# 07_nRF_GPIO.net
KiCad netlist of a schematic drawn in Altium Designer
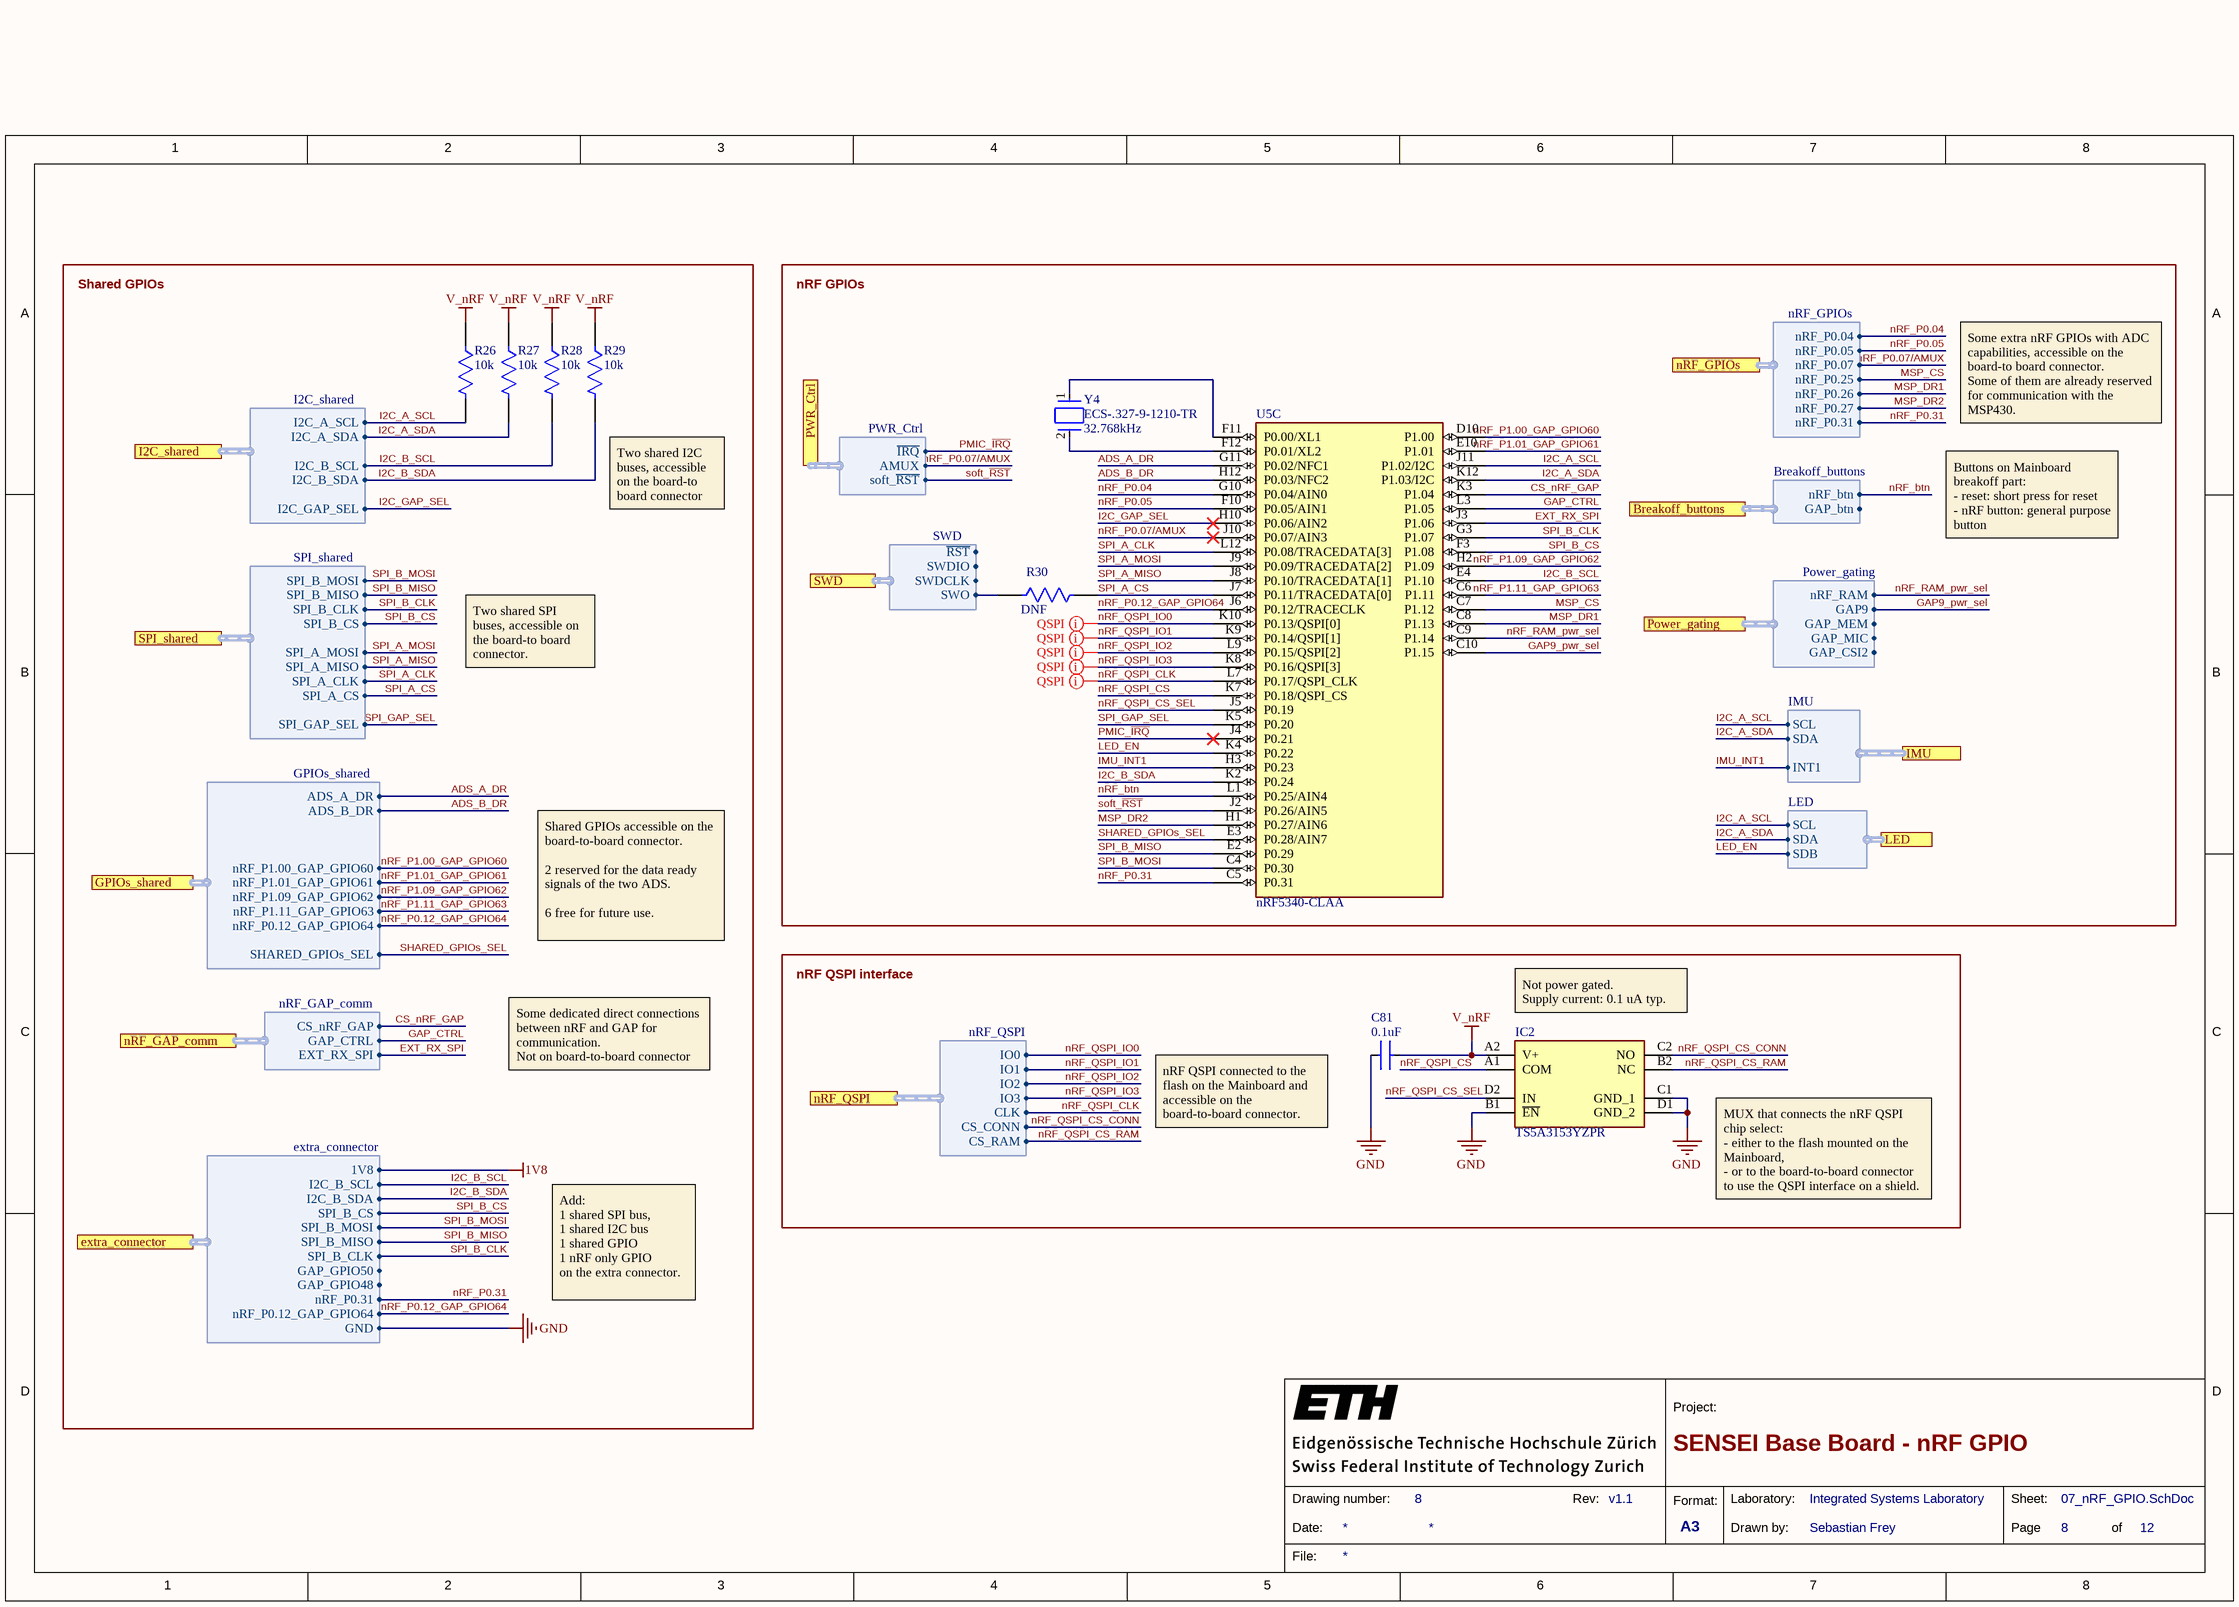
[diagram p0: 07_nRF_GPIO.SchDoc]

(export (version "E")
  (design (tool "Eeschema 10.0.6"))
  (components
    (comp (ref "C81")
      (value "GRM033Z71C104KE14D")
      (footprint "FP-GRM033-0_03-IPC_C")
      (description "Chip Multilayer Ceramic Capacitors for General Purpose, 0201, 0.10uF, X7R, 15%, 10%, 16V")
      (fields (field (name "CAPACITANCE") "0.1uF"))
      (libsource (lib "Altium Content Vault") (part "b4654b650e69147ec39a6b967a45e02"))
    )
    (comp (ref "IC2")
      (value "TS5A3153YZPR")
      (footprint "SamacSys:BGA8C50P2X4_89X189X50")
      (description "Integrated Circuit")
      (fields (field (name "MOUSER PART NUMBER") "595-TS5A3153YZPR"))
      (libsource (lib "SamacSys") (part "TS5A3153YZPR"))
    )
    (comp (ref "R26")
      (value "RMCF0201FT10K0")
      (footprint "FP-RMCF0201-IPC_C")
      (description "RES 10K OHM 1% 1/20W 0201")
      (fields (field (name "RESISTANCE") "10k") (field (name "TOLERANCE") "1%"))
      (libsource (lib "Altium Content Vault") (part "1029c3af85768c4190bb7ad29bc67b5"))
    )
    (comp (ref "R27")
      (value "RMCF0201FT10K0")
      (footprint "FP-RMCF0201-IPC_C")
      (description "RES 10K OHM 1% 1/20W 0201")
      (fields (field (name "RESISTANCE") "10k") (field (name "TOLERANCE") "1%"))
      (libsource (lib "Altium Content Vault") (part "1029c3af85768c4190bb7ad29bc67b5"))
    )
    (comp (ref "R28")
      (value "RMCF0201FT10K0")
      (footprint "FP-RMCF0201-IPC_C")
      (description "RES 10K OHM 1% 1/20W 0201")
      (fields (field (name "RESISTANCE") "10k") (field (name "TOLERANCE") "1%"))
      (libsource (lib "Altium Content Vault") (part "1029c3af85768c4190bb7ad29bc67b5"))
    )
    (comp (ref "R29")
      (value "RMCF0201FT10K0")
      (footprint "FP-RMCF0201-IPC_C")
      (description "RES 10K OHM 1% 1/20W 0201")
      (fields (field (name "RESISTANCE") "10k") (field (name "TOLERANCE") "1%"))
      (libsource (lib "Altium Content Vault") (part "1029c3af85768c4190bb7ad29bc67b5"))
    )
    (comp (ref "R30")
      (value "DNF")
      (footprint "FP-RMCF0201-IPC_C")
      (libsource (lib "Altium Content Vault") (part "1029c3af85768c4190bb7ad29bc67b5"))
    )
    (comp (ref "U5")
      (value "nRF5340-CLAA")
      (footprint "EEG_PcbLib:NRF5340_WLCSP")
      (description "Multi-protocol Bluetooth Low Energy, IEEE 802.15.4, ANT and 2.4GHz proprietary system-on-chip")
      (fields
        (field (name "MANUFACTURER") "Nordic")
        (field (name "MANUFACTURER PART NUMBER") "NRF5340-CLAA-R7")
      )
      (libsource (lib "EEG_SchLib") (part "nRF5340-CLAA"))
    )
    (comp (ref "Y4")
      (value "ECS-.327-9-1210-TR")
      (footprint "FP-ECX-1210-MFG")
      (description "CRYSTAL 32.7680KHZ 9PF SMD")
      (fields (field (name "FREQUENCY") "32.768kHz"))
      (libsource (lib "Altium Content Vault") (part "99724985039315a44fd0d1401b84e49"))
    )
  )
  (nets
    (net (code "14") (name "/ADS_A_DR") (class "Default")
      (node (ref "U5") (pin "G11") (pinfunction "P0.02/NFC1_G11") (pintype "bidirectional"))
    )
    (net (code "15") (name "/ADS_B_DR") (class "Default")
      (node (ref "U5") (pin "H12") (pinfunction "P0.03/NFC2_H12") (pintype "bidirectional"))
    )
    (net (code "16") (name "/CS_nRF_GAP") (class "Default")
      (node (ref "U5") (pin "K3") (pinfunction "P1.04_K3") (pintype "bidirectional"))
    )
    (net (code "17") (name "/EXT_RX_SPI") (class "Default")
      (node (ref "U5") (pin "J3") (pinfunction "P1.06_J3") (pintype "bidirectional"))
    )
    (net (code "18") (name "/GAP9_pwr_sel") (class "Default")
      (node (ref "U5") (pin "C10") (pinfunction "P1.15_C10") (pintype "bidirectional"))
    )
    (net (code "19") (name "/GAP_CTRL") (class "Default")
      (node (ref "U5") (pin "L3") (pinfunction "P1.05_L3") (pintype "bidirectional"))
    )
    (net (code "20") (name "/I2C_A_SCL") (class "Default")
      (node (ref "R26") (pin "2") (pinfunction "2_2") (pintype "passive"))
      (node (ref "U5") (pin "J11") (pinfunction "P1.02/I2C_J11") (pintype "bidirectional"))
    )
    (net (code "21") (name "/I2C_A_SDA") (class "Default")
      (node (ref "R27") (pin "2") (pinfunction "2_2") (pintype "passive"))
      (node (ref "U5") (pin "K12") (pinfunction "P1.03/I2C_K12") (pintype "bidirectional"))
    )
    (net (code "22") (name "/I2C_B_SCL") (class "Default")
      (node (ref "R28") (pin "2") (pinfunction "2_2") (pintype "passive"))
      (node (ref "U5") (pin "E4") (pinfunction "P1.10_E4") (pintype "bidirectional"))
    )
    (net (code "23") (name "/I2C_B_SDA") (class "Default")
      (node (ref "R29") (pin "2") (pinfunction "2_2") (pintype "passive"))
      (node (ref "U5") (pin "K2") (pinfunction "P0.24_K2") (pintype "bidirectional"))
    )
    (net (code "24") (name "/I2C_GAP_SEL") (class "Default")
      (node (ref "U5") (pin "H10") (pinfunction "P0.06/AIN2_H10") (pintype "bidirectional+no_connect"))
    )
    (net (code "25") (name "/IMU_INT1") (class "Default")
      (node (ref "U5") (pin "H3") (pinfunction "P0.23_H3") (pintype "bidirectional"))
    )
    (net (code "26") (name "/LED_EN") (class "Default")
      (node (ref "U5") (pin "K4") (pinfunction "P0.22_K4") (pintype "bidirectional"))
    )
    (net (code "27") (name "/MSP_CS") (class "Default")
      (node (ref "U5") (pin "C7") (pinfunction "P1.12_C7") (pintype "bidirectional"))
    )
    (net (code "28") (name "/MSP_DR1") (class "Default")
      (node (ref "U5") (pin "C8") (pinfunction "P1.13_C8") (pintype "bidirectional"))
    )
    (net (code "29") (name "/MSP_DR2") (class "Default")
      (node (ref "U5") (pin "H1") (pinfunction "P0.27/AIN6_H1") (pintype "bidirectional"))
    )
    (net (code "30") (name "/PMIC_~{IRQ}") (class "Default")
      (node (ref "U5") (pin "J4") (pinfunction "P0.21_J4") (pintype "bidirectional+no_connect"))
    )
    (net (code "31") (name "/SHARED_GPIOs_SEL") (class "Default")
      (node (ref "U5") (pin "E3") (pinfunction "P0.28/AIN7_E3") (pintype "bidirectional"))
    )
    (net (code "32") (name "/SPI_A_CLK") (class "Default")
      (node (ref "U5") (pin "L12") (pinfunction "P0.08/TRACEDATA[3]_L12") (pintype "bidirectional"))
    )
    (net (code "33") (name "/SPI_A_CS") (class "Default")
      (node (ref "R30") (pin "2") (pinfunction "2_2") (pintype "passive"))
      (node (ref "U5") (pin "J7") (pinfunction "P0.11/TRACEDATA[0]_J7") (pintype "bidirectional"))
    )
    (net (code "34") (name "/SPI_A_MISO") (class "Default")
      (node (ref "U5") (pin "J8") (pinfunction "P0.10/TRACEDATA[1]_J8") (pintype "bidirectional"))
    )
    (net (code "35") (name "/SPI_A_MOSI") (class "Default")
      (node (ref "U5") (pin "J9") (pinfunction "P0.09/TRACEDATA[2]_J9") (pintype "bidirectional"))
    )
    (net (code "36") (name "/SPI_B_CLK") (class "Default")
      (node (ref "U5") (pin "G3") (pinfunction "P1.07_G3") (pintype "bidirectional"))
    )
    (net (code "37") (name "/SPI_B_CS") (class "Default")
      (node (ref "U5") (pin "F3") (pinfunction "P1.08_F3") (pintype "bidirectional"))
    )
    (net (code "38") (name "/SPI_B_MISO") (class "Default")
      (node (ref "U5") (pin "E2") (pinfunction "P0.29_E2") (pintype "bidirectional"))
    )
    (net (code "39") (name "/SPI_B_MOSI") (class "Default")
      (node (ref "U5") (pin "C4") (pinfunction "P0.30_C4") (pintype "bidirectional"))
    )
    (net (code "40") (name "/SPI_GAP_SEL") (class "Default")
      (node (ref "U5") (pin "K5") (pinfunction "P0.20_K5") (pintype "bidirectional"))
    )
    (net (code "41") (name "/nRF_P0.04") (class "Default")
      (node (ref "U5") (pin "G10") (pinfunction "P0.04/AIN0_G10") (pintype "bidirectional"))
    )
    (net (code "42") (name "/nRF_P0.05") (class "Default")
      (node (ref "U5") (pin "F10") (pinfunction "P0.05/AIN1_F10") (pintype "bidirectional"))
    )
    (net (code "43") (name "/nRF_P0.07{slash}AMUX") (class "Default")
      (node (ref "U5") (pin "J10") (pinfunction "P0.07/AIN3_J10") (pintype "bidirectional"))
    )
    (net (code "44") (name "/nRF_P0.12_GAP_GPIO64") (class "Default")
      (node (ref "U5") (pin "J6") (pinfunction "P0.12/TRACECLK_J6") (pintype "bidirectional"))
    )
    (net (code "45") (name "/nRF_P0.31") (class "Default")
      (node (ref "U5") (pin "C5") (pinfunction "P0.31_C5") (pintype "bidirectional"))
    )
    (net (code "46") (name "/nRF_P1.00_GAP_GPIO60") (class "Default")
      (node (ref "U5") (pin "D10") (pinfunction "P1.00_D10") (pintype "bidirectional"))
    )
    (net (code "47") (name "/nRF_P1.01_GAP_GPIO61") (class "Default")
      (node (ref "U5") (pin "E10") (pinfunction "P1.01_E10") (pintype "bidirectional"))
    )
    (net (code "48") (name "/nRF_P1.09_GAP_GPIO62") (class "Default")
      (node (ref "U5") (pin "H2") (pinfunction "P1.09_H2") (pintype "bidirectional"))
    )
    (net (code "49") (name "/nRF_P1.11_GAP_GPIO63") (class "Default")
      (node (ref "U5") (pin "C6") (pinfunction "P1.11_C6") (pintype "bidirectional"))
    )
    (net (code "50") (name "/nRF_QSPI_CLK") (class "Default")
      (node (ref "U5") (pin "L7") (pinfunction "P0.17/QSPI_CLK_L7") (pintype "bidirectional"))
    )
    (net (code "51") (name "/nRF_QSPI_CS") (class "Default")
      (node (ref "IC2") (pin "A1") (pinfunction "COM_A1") (pintype "passive"))
      (node (ref "U5") (pin "K7") (pinfunction "P0.18/QSPI_CS_K7") (pintype "bidirectional"))
    )
    (net (code "52") (name "/nRF_QSPI_CS_CONN") (class "Default")
      (node (ref "IC2") (pin "C2") (pinfunction "NO_C2") (pintype "passive"))
    )
    (net (code "53") (name "/nRF_QSPI_CS_RAM") (class "Default")
      (node (ref "IC2") (pin "B2") (pinfunction "NC_B2") (pintype "passive"))
    )
    (net (code "54") (name "/nRF_QSPI_CS_SEL") (class "Default")
      (node (ref "IC2") (pin "D2") (pinfunction "IN_D2") (pintype "passive"))
      (node (ref "U5") (pin "J5") (pinfunction "P0.19_J5") (pintype "bidirectional"))
    )
    (net (code "55") (name "/nRF_QSPI_IO0") (class "Default")
      (node (ref "U5") (pin "K10") (pinfunction "P0.13/QSPI[0]_K10") (pintype "bidirectional"))
    )
    (net (code "56") (name "/nRF_QSPI_IO1") (class "Default")
      (node (ref "U5") (pin "K9") (pinfunction "P0.14/QSPI[1]_K9") (pintype "bidirectional"))
    )
    (net (code "57") (name "/nRF_QSPI_IO2") (class "Default")
      (node (ref "U5") (pin "L9") (pinfunction "P0.15/QSPI[2]_L9") (pintype "bidirectional"))
    )
    (net (code "58") (name "/nRF_QSPI_IO3") (class "Default")
      (node (ref "U5") (pin "K8") (pinfunction "P0.16/QSPI[3]_K8") (pintype "bidirectional"))
    )
    (net (code "59") (name "/nRF_RAM_pwr_sel") (class "Default")
      (node (ref "U5") (pin "C9") (pinfunction "P1.14_C9") (pintype "bidirectional"))
    )
    (net (code "60") (name "/nRF_btn") (class "Default")
      (node (ref "U5") (pin "L1") (pinfunction "P0.25/AIN4_L1") (pintype "bidirectional"))
    )
    (net (code "61") (name "/soft_~{RST}") (class "Default")
      (node (ref "U5") (pin "J2") (pinfunction "P0.26/AIN5_J2") (pintype "bidirectional"))
    )
    (net (code "76") (name "GND") (class "Default")
      (node (ref "C81") (pin "2") (pinfunction "2_2") (pintype "passive"))
      (node (ref "IC2") (pin "B1") (pinfunction "~{EN}_B1") (pintype "passive"))
      (node (ref "IC2") (pin "C1") (pinfunction "GND_1_C1") (pintype "passive"))
      (node (ref "IC2") (pin "D1") (pinfunction "GND_2_D1") (pintype "passive"))
    )
    (net (code "77") (name "Net-(U5C-P0.00{slash}XL1)") (class "Default")
      (node (ref "U5") (pin "F11") (pinfunction "P0.00/XL1_F11") (pintype "bidirectional"))
      (node (ref "Y4") (pin "1") (pinfunction "In/Out_1") (pintype "passive"))
    )
    (net (code "78") (name "Net-(U5C-P0.01{slash}XL2)") (class "Default")
      (node (ref "U5") (pin "F12") (pinfunction "P0.01/XL2_F12") (pintype "bidirectional"))
      (node (ref "Y4") (pin "2") (pinfunction "Out/In_2") (pintype "passive"))
    )
    (net (code "79") (name "V_nRF") (class "Default")
      (node (ref "C81") (pin "1") (pinfunction "1_1") (pintype "passive"))
      (node (ref "IC2") (pin "A2") (pinfunction "V+_A2") (pintype "passive"))
      (node (ref "R26") (pin "1") (pinfunction "1_1") (pintype "passive"))
      (node (ref "R27") (pin "1") (pinfunction "1_1") (pintype "passive"))
      (node (ref "R28") (pin "1") (pinfunction "1_1") (pintype "passive"))
      (node (ref "R29") (pin "1") (pinfunction "1_1") (pintype "passive"))
    )
    (net (code "80") (name "unconnected-(R30-Pad1)") (class "Default")
      (node (ref "R30") (pin "1") (pinfunction "1_1") (pintype "passive"))
    )
  )
)
